# MCU.net
KiCad netlist of a schematic drawn in EAGLE
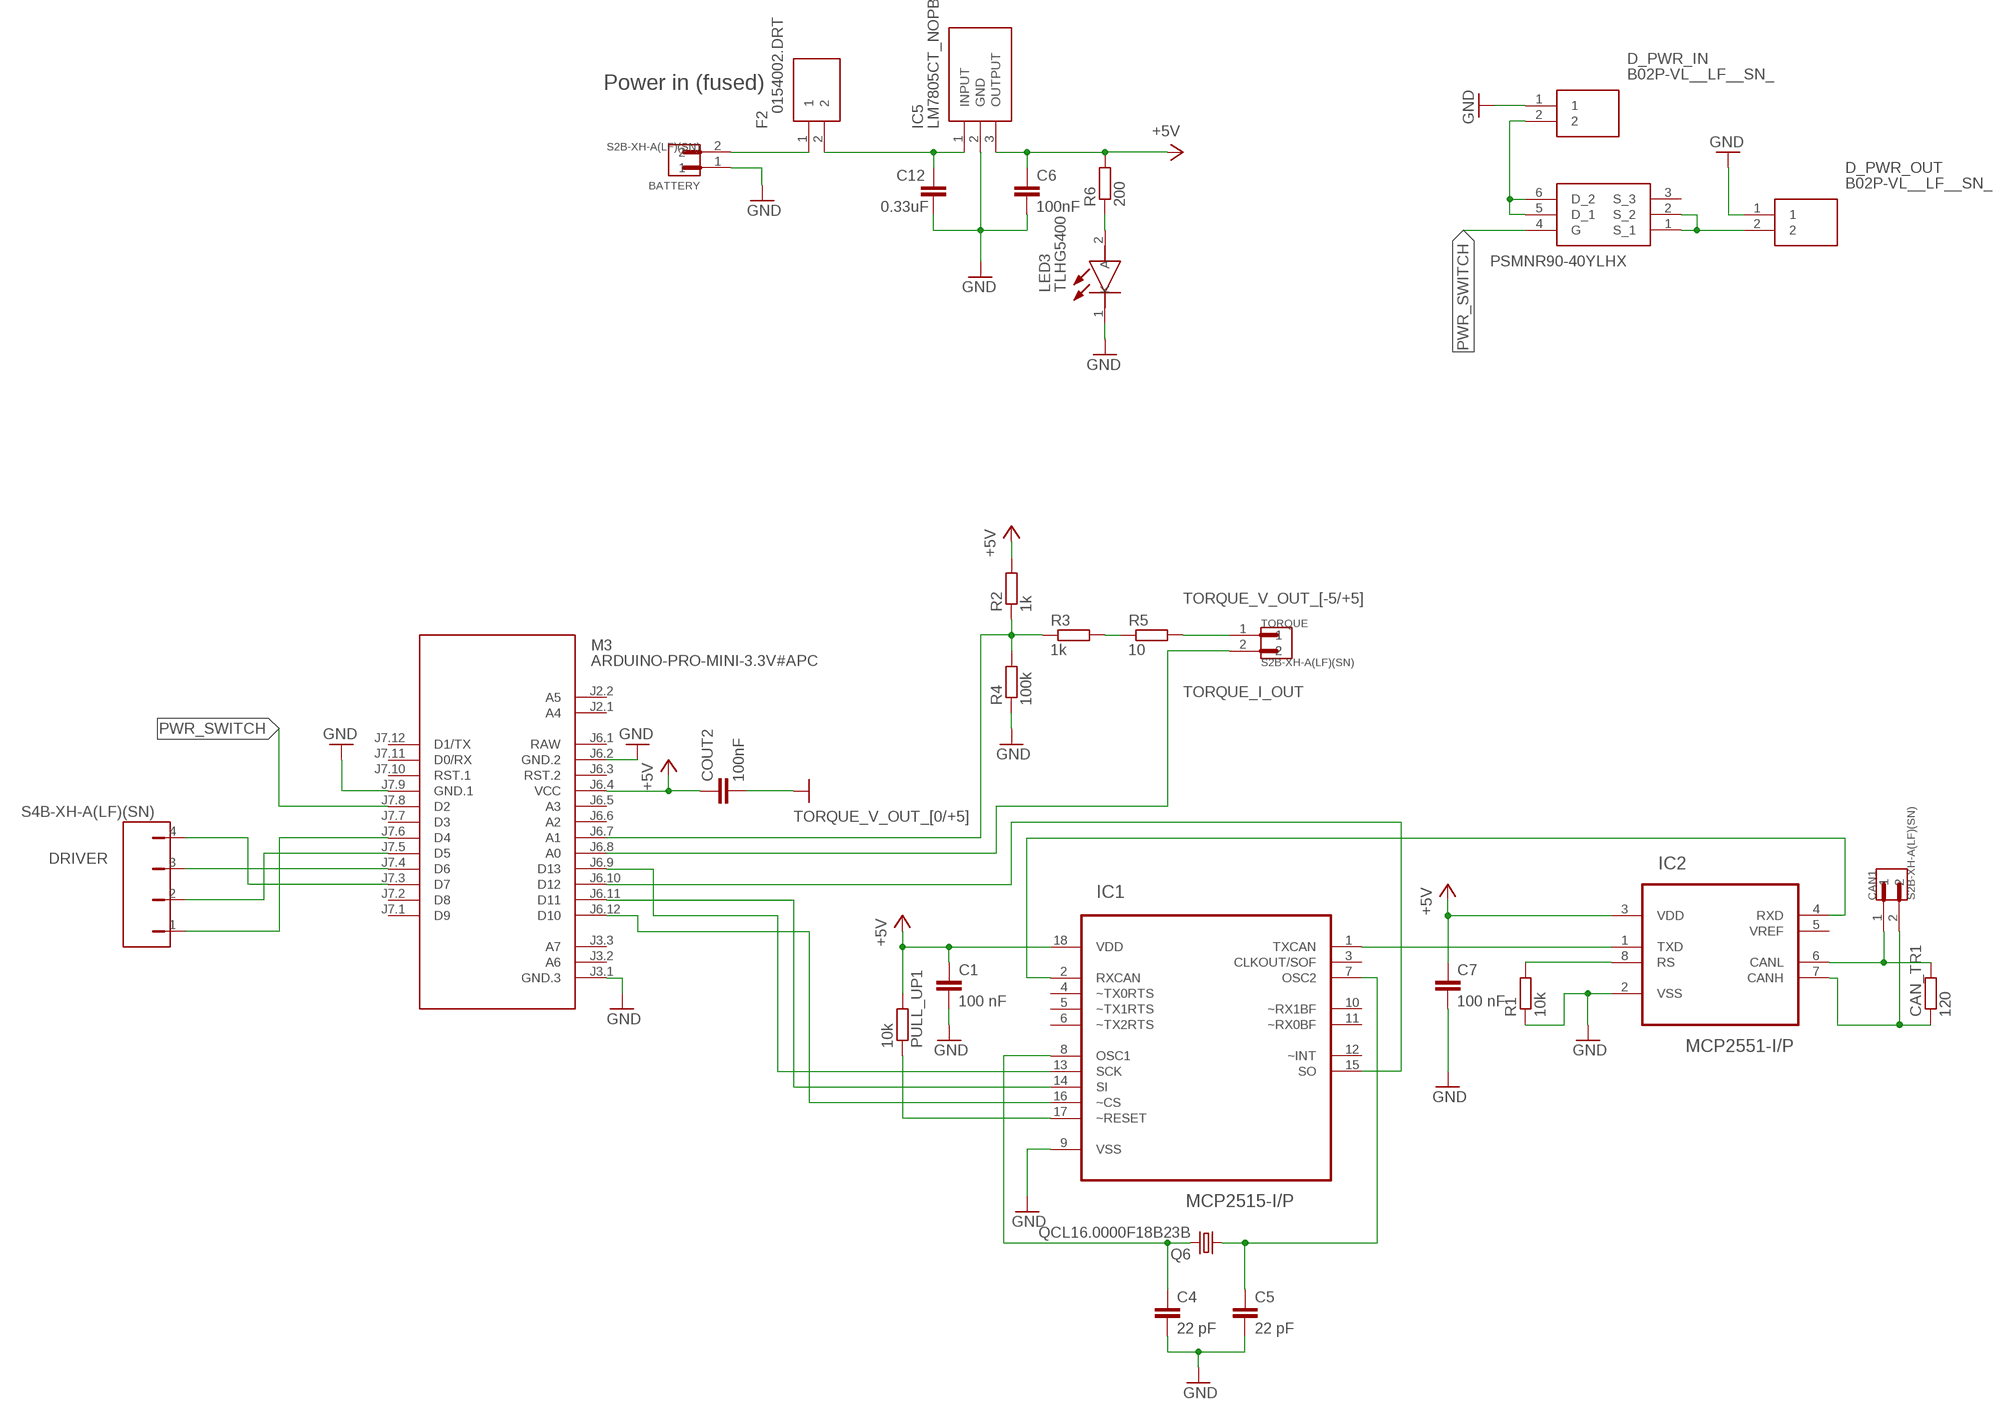
[diagram p0: schematic, sheet 1]

(export (version "E")
  (design (tool "Eeschema 10.0.6"))
  (components
    (comp (ref "BATTERY")
      (value "S2B-XH-A(LF)(SN)")
      (footprint "eagle-import:JST_S2B-XH-A(LF)(SN)")
      (fields
        (field (name "DIGI-KEY_PART_NUMBER") "455-2257-ND")
        (field (name "MF") "JST Sales")
        (field (name "MP") "S2B-XH-A_LF__SN_")
      )
      (libsource (lib "eagle-import") (part "S2B-XH-A(LF)(SN)"))
    )
    (comp (ref "C1")
      (value "100 nF")
      (footprint "eagle-import:C0805")
      (libsource (lib "eagle-import") (part "C-EUC0805"))
    )
    (comp (ref "C4")
      (value "22 pF")
      (footprint "eagle-import:C0805")
      (libsource (lib "eagle-import") (part "C-EUC0805"))
    )
    (comp (ref "C5")
      (value "22 pF")
      (footprint "eagle-import:C0805")
      (libsource (lib "eagle-import") (part "C-EUC0805"))
    )
    (comp (ref "C6")
      (value "100nF")
      (footprint "eagle-import:C0805")
      (libsource (lib "eagle-import") (part "C-EUC0805"))
    )
    (comp (ref "C7")
      (value "100 nF")
      (footprint "eagle-import:C0805")
      (libsource (lib "eagle-import") (part "C-EUC0805"))
    )
    (comp (ref "C12")
      (value "0.33uF")
      (footprint "eagle-import:C0805")
      (libsource (lib "eagle-import") (part "C-EUC0805"))
    )
    (comp (ref "CAN1")
      (value "S2B-XH-A(LF)(SN)")
      (footprint "eagle-import:JST_S2B-XH-A(LF)(SN)")
      (fields
        (field (name "DIGI-KEY_PART_NUMBER") "455-2257-ND")
        (field (name "MF") "JST Sales")
        (field (name "MP") "S2B-XH-A_LF__SN_")
      )
      (libsource (lib "eagle-import") (part "S2B-XH-A(LF)(SN)"))
    )
    (comp (ref "CAN_TR1")
      (value "120")
      (footprint "eagle-import:R0805")
      (libsource (lib "eagle-import") (part "R-EU_R0805"))
    )
    (comp (ref "COUT2")
      (value "100nF")
      (footprint "eagle-import:C0805")
      (libsource (lib "eagle-import") (part "C-EUC0805"))
    )
    (comp (ref "DRIVER")
      (value "S4B-XH-A(LF)(SN)")
      (footprint "eagle-import:S4B-XH-A(LF)(SN)")
      (fields (field (name "MF") "JST Sales") (field (name "MP") "S4B-XH-A_LF__SN_"))
      (libsource (lib "eagle-import") (part "S4B-XH-A(LF)(SN)"))
    )
    (comp (ref "D_PWR_IN")
      (value "B02P-VL__LF__SN_")
      (footprint "eagle-import:SHDR2W180P0X620_1X2_1340X1320X")
      (fields
        (field (name "MANUFACTURER_PART_NUMBER") "B02P-VL (LF)(SN)")
        (field (name "RS_PART_NUMBER") "8201093P")
      )
      (libsource (lib "eagle-import") (part "B02P-VL__LF__SN_"))
    )
    (comp (ref "D_PWR_OUT")
      (value "B02P-VL__LF__SN_")
      (footprint "eagle-import:SHDR2W180P0X620_1X2_1340X1320X")
      (fields
        (field (name "MANUFACTURER_PART_NUMBER") "B02P-VL (LF)(SN)")
        (field (name "RS_PART_NUMBER") "8201093P")
      )
      (libsource (lib "eagle-import") (part "B02P-VL__LF__SN_"))
    )
    (comp (ref "F2")
      (value "0154002.DRT")
      (footprint "eagle-import:FUSM9750X381N")
      (fields (field (name "MOUSER_PART_NUMBER") "576-0154002.DRT"))
      (libsource (lib "eagle-import") (part "0154002.DRT"))
    )
    (comp (ref "IC1")
      (value "MCP2515-I/P")
      (footprint "eagle-import:DIP254P762X432-18")
      (fields (field (name "MF") "Microchip"))
      (libsource (lib "eagle-import") (part "MCP2515-I/P"))
    )
    (comp (ref "IC2")
      (value "MCP2551-I/P")
      (footprint "eagle-import:DIP254P762X432-8")
      (fields (field (name "MF") "Microchip"))
      (libsource (lib "eagle-import") (part "MCP2551-I/P"))
    )
    (comp (ref "IC5")
      (value "LM7805CT_NOPB")
      (footprint "eagle-import:TO254P470X1028X1955-3P")
      (fields
        (field (name "MANUFACTURER_PART_NUMBER") "LM7805CT/NOPB")
        (field (name "MOUSER_PART_NUMBER") "926-LM7805CT/NOPB")
      )
      (libsource (lib "eagle-import") (part "LM7805CT_NOPB"))
    )
    (comp (ref "LED3")
      (value "TLHG5400")
      (footprint "eagle-import:TLHG5400")
      (fields (field (name "MOUSER_PART_NUMBER") "78-TLHG5400"))
      (libsource (lib "eagle-import") (part "TLHG5400"))
    )
    (comp (ref "M3")
      (value "ARDUINO-PRO-MINI-3.3V#APC")
      (footprint "eagle-import:ARDUINO-PRO-MINI#APC")
      (libsource (lib "eagle-import") (part "ARDUINO-PRO-MINI-#APC3.3V"))
    )
    (comp (ref "PULL_UP1")
      (value "10k")
      (footprint "eagle-import:R0805")
      (libsource (lib "eagle-import") (part "R-EU_R0805"))
    )
    (comp (ref "Q1")
      (value "PSMNR90-40YLHX")
      (footprint "eagle-import:PSMNR9040YLHX")
      (fields (field (name "MOUSER_PART_NUMBER") "771-PSMNR90-40YLHX"))
      (libsource (lib "eagle-import") (part "PSMNR90-40YLHX"))
    )
    (comp (ref "Q6")
      (value "QCL16.0000F18B23B")
      (footprint "eagle-import:HC49_S")
      (libsource (lib "eagle-import") (part "CRYSTALHC49S"))
    )
    (comp (ref "R1")
      (value "10k")
      (footprint "eagle-import:R0805")
      (libsource (lib "eagle-import") (part "R-EU_R0805"))
    )
    (comp (ref "R2")
      (value "1k")
      (footprint "eagle-import:R0805")
      (libsource (lib "eagle-import") (part "R-EU_R0805"))
    )
    (comp (ref "R3")
      (value "1k")
      (footprint "eagle-import:R0805")
      (libsource (lib "eagle-import") (part "R-EU_R0805"))
    )
    (comp (ref "R4")
      (value "100k")
      (footprint "eagle-import:R0805")
      (libsource (lib "eagle-import") (part "R-EU_R0805"))
    )
    (comp (ref "R5")
      (value "10")
      (footprint "eagle-import:R0805")
      (libsource (lib "eagle-import") (part "R-EU_R0805"))
    )
    (comp (ref "R6")
      (value "200")
      (footprint "eagle-import:R0805")
      (libsource (lib "eagle-import") (part "R-EU_R0805"))
    )
    (comp (ref "TORQUE")
      (value "S2B-XH-A(LF)(SN)")
      (footprint "eagle-import:JST_S2B-XH-A(LF)(SN)")
      (fields
        (field (name "DIGI-KEY_PART_NUMBER") "455-2257-ND")
        (field (name "MF") "JST Sales")
        (field (name "MP") "S2B-XH-A_LF__SN_")
      )
      (libsource (lib "eagle-import") (part "S2B-XH-A(LF)(SN)"))
    )
  )
  (nets
    (net (code "1") (name "+5V") (class "Default")
      (node (ref "C1") (pin "1") (pinfunction "1_1") (pintype "passive"))
      (node (ref "C6") (pin "1") (pinfunction "1_1") (pintype "passive"))
      (node (ref "C7") (pin "1") (pinfunction "1_1") (pintype "passive"))
      (node (ref "COUT2") (pin "1") (pinfunction "1_1") (pintype "passive"))
      (node (ref "IC1") (pin "18") (pinfunction "VDD_18") (pintype "power_in"))
      (node (ref "IC2") (pin "3") (pinfunction "VDD_3") (pintype "power_in"))
      (node (ref "IC5") (pin "3") (pinfunction "OUTPUT_3") (pintype "bidirectional"))
      (node (ref "M3") (pin "J6.4") (pinfunction "VCC_J6.4") (pintype "power_in"))
      (node (ref "PULL_UP1") (pin "2") (pinfunction "2_2") (pintype "passive"))
      (node (ref "R2") (pin "2") (pinfunction "2_2") (pintype "passive"))
      (node (ref "R6") (pin "2") (pinfunction "2_2") (pintype "passive"))
    )
    (net (code "2") (name "/RAW") (class "Default")
      (node (ref "M3") (pin "J6.1") (pinfunction "RAW_J6.1") (pintype "power_in"))
    )
    (net (code "3") (name "/TORQUE_I_OUT") (class "Default")
      (node (ref "M3") (pin "J6.8") (pinfunction "A0_J6.8") (pintype "bidirectional"))
      (node (ref "TORQUE") (pin "2") (pinfunction "2_2") (pintype "passive"))
    )
    (net (code "4") (name "/TORQUE_V_OUT_[-5{slash}+5]") (class "Default")
      (node (ref "R5") (pin "2") (pinfunction "2_2") (pintype "passive"))
      (node (ref "TORQUE") (pin "1") (pinfunction "1_1") (pintype "passive"))
    )
    (net (code "5") (name "/TORQUE_V_OUT_[0{slash}+5]") (class "Default")
      (node (ref "M3") (pin "J6.7") (pinfunction "A1_J6.7") (pintype "bidirectional"))
      (node (ref "R2") (pin "1") (pinfunction "1_1") (pintype "passive"))
      (node (ref "R3") (pin "1") (pinfunction "1_1") (pintype "passive"))
      (node (ref "R4") (pin "2") (pinfunction "2_2") (pintype "passive"))
    )
    (net (code "6") (name "GND") (class "Default")
      (node (ref "BATTERY") (pin "1") (pinfunction "1_1") (pintype "passive"))
      (node (ref "C1") (pin "2") (pinfunction "2_2") (pintype "passive"))
      (node (ref "C12") (pin "2") (pinfunction "2_2") (pintype "passive"))
      (node (ref "C4") (pin "2") (pinfunction "2_2") (pintype "passive"))
      (node (ref "C5") (pin "2") (pinfunction "2_2") (pintype "passive"))
      (node (ref "C6") (pin "2") (pinfunction "2_2") (pintype "passive"))
      (node (ref "C7") (pin "2") (pinfunction "2_2") (pintype "passive"))
      (node (ref "COUT2") (pin "2") (pinfunction "2_2") (pintype "passive"))
      (node (ref "D_PWR_IN") (pin "1") (pinfunction "1_1") (pintype "bidirectional"))
      (node (ref "D_PWR_OUT") (pin "1") (pinfunction "1_1") (pintype "bidirectional"))
      (node (ref "IC1") (pin "9") (pinfunction "VSS_9") (pintype "power_in"))
      (node (ref "IC2") (pin "2") (pinfunction "VSS_2") (pintype "power_in"))
      (node (ref "IC5") (pin "2") (pinfunction "GND_2") (pintype "bidirectional"))
      (node (ref "LED3") (pin "1") (pinfunction "K_1") (pintype "bidirectional"))
      (node (ref "M3") (pin "J3.1") (pinfunction "GND.3_J3.1") (pintype "bidirectional"))
      (node (ref "M3") (pin "J6.2") (pinfunction "GND.2_J6.2") (pintype "power_in"))
      (node (ref "M3") (pin "J7.9") (pinfunction "GND.1_J7.9") (pintype "power_in"))
      (node (ref "R1") (pin "1") (pinfunction "1_1") (pintype "passive"))
      (node (ref "R4") (pin "1") (pinfunction "1_1") (pintype "passive"))
    )
    (net (code "7") (name "Net-(BATTERY-Pad2)") (class "Default")
      (node (ref "BATTERY") (pin "2") (pinfunction "2_2") (pintype "passive"))
      (node (ref "F2") (pin "1") (pinfunction "1_1") (pintype "bidirectional"))
    )
    (net (code "8") (name "Net-(IC1-OSC1)") (class "Default")
      (node (ref "C4") (pin "1") (pinfunction "1_1") (pintype "passive"))
      (node (ref "IC1") (pin "8") (pinfunction "OSC1_8") (pintype "input"))
      (node (ref "Q6") (pin "2") (pinfunction "2_2") (pintype "passive"))
    )
    (net (code "9") (name "Net-(IC1-OSC2)") (class "Default")
      (node (ref "C5") (pin "1") (pinfunction "1_1") (pintype "passive"))
      (node (ref "IC1") (pin "7") (pinfunction "OSC2_7") (pintype "output"))
      (node (ref "Q6") (pin "1") (pinfunction "1_1") (pintype "passive"))
    )
    (net (code "10") (name "Net-(IC1-RXCAN)") (class "Default")
      (node (ref "IC1") (pin "2") (pinfunction "RXCAN_2") (pintype "input"))
      (node (ref "IC2") (pin "4") (pinfunction "RXD_4") (pintype "output"))
    )
    (net (code "11") (name "Net-(IC1-SCK)") (class "Default")
      (node (ref "IC1") (pin "13") (pinfunction "SCK_13") (pintype "input"))
      (node (ref "M3") (pin "J6.9") (pinfunction "D13_J6.9") (pintype "bidirectional"))
    )
    (net (code "12") (name "Net-(IC1-SI)") (class "Default")
      (node (ref "IC1") (pin "14") (pinfunction "SI_14") (pintype "input"))
      (node (ref "M3") (pin "J6.11") (pinfunction "D11_J6.11") (pintype "bidirectional"))
    )
    (net (code "13") (name "Net-(IC1-SO)") (class "Default")
      (node (ref "IC1") (pin "15") (pinfunction "SO_15") (pintype "output"))
      (node (ref "M3") (pin "J6.10") (pinfunction "D12_J6.10") (pintype "bidirectional"))
    )
    (net (code "14") (name "Net-(IC1-TXCAN)") (class "Default")
      (node (ref "IC1") (pin "1") (pinfunction "TXCAN_1") (pintype "output"))
      (node (ref "IC2") (pin "1") (pinfunction "TXD_1") (pintype "input"))
    )
    (net (code "15") (name "Net-(IC1-~{CS})") (class "Default")
      (node (ref "IC1") (pin "16") (pinfunction "~{CS}_16") (pintype "input"))
      (node (ref "M3") (pin "J6.12") (pinfunction "D10_J6.12") (pintype "bidirectional"))
    )
    (net (code "16") (name "Net-(IC1-~{RESET})") (class "Default")
      (node (ref "IC1") (pin "17") (pinfunction "~{RESET}_17") (pintype "input"))
      (node (ref "PULL_UP1") (pin "1") (pinfunction "1_1") (pintype "passive"))
    )
    (net (code "17") (name "Net-(IC2-CANH)") (class "Default")
      (node (ref "CAN1") (pin "2") (pinfunction "2_2") (pintype "passive"))
      (node (ref "CAN_TR1") (pin "1") (pinfunction "1_1") (pintype "passive"))
      (node (ref "IC2") (pin "7") (pinfunction "CANH_7") (pintype "bidirectional"))
    )
    (net (code "18") (name "Net-(IC2-CANL)") (class "Default")
      (node (ref "CAN1") (pin "1") (pinfunction "1_1") (pintype "passive"))
      (node (ref "CAN_TR1") (pin "2") (pinfunction "2_2") (pintype "passive"))
      (node (ref "IC2") (pin "6") (pinfunction "CANL_6") (pintype "bidirectional"))
    )
    (net (code "19") (name "Net-(IC2-RS)") (class "Default")
      (node (ref "IC2") (pin "8") (pinfunction "RS_8") (pintype "input"))
      (node (ref "R1") (pin "2") (pinfunction "2_2") (pintype "passive"))
    )
    (net (code "20") (name "Net-(IC5-INPUT)") (class "Default")
      (node (ref "C12") (pin "1") (pinfunction "1_1") (pintype "passive"))
      (node (ref "F2") (pin "2") (pinfunction "2_2") (pintype "bidirectional"))
      (node (ref "IC5") (pin "1") (pinfunction "INPUT_1") (pintype "bidirectional"))
    )
    (net (code "21") (name "Net-(LED3-A)") (class "Default")
      (node (ref "LED3") (pin "2") (pinfunction "A_2") (pintype "bidirectional"))
      (node (ref "R6") (pin "1") (pinfunction "1_1") (pintype "passive"))
    )
    (net (code "22") (name "Net-(M3-D4)") (class "Default")
      (node (ref "DRIVER") (pin "1") (pinfunction "1_1") (pintype "passive"))
      (node (ref "M3") (pin "J7.6") (pinfunction "D4_J7.6") (pintype "bidirectional"))
    )
    (net (code "23") (name "Net-(M3-D5)") (class "Default")
      (node (ref "DRIVER") (pin "2") (pinfunction "2_2") (pintype "passive"))
      (node (ref "M3") (pin "J7.5") (pinfunction "D5_J7.5") (pintype "bidirectional"))
    )
    (net (code "24") (name "Net-(M3-D6)") (class "Default")
      (node (ref "DRIVER") (pin "3") (pinfunction "3_3") (pintype "passive"))
      (node (ref "M3") (pin "J7.4") (pinfunction "D6_J7.4") (pintype "bidirectional"))
    )
    (net (code "25") (name "Net-(M3-D7)") (class "Default")
      (node (ref "DRIVER") (pin "4") (pinfunction "4_4") (pintype "passive"))
      (node (ref "M3") (pin "J7.3") (pinfunction "D7_J7.3") (pintype "bidirectional"))
    )
    (net (code "26") (name "Net-(Q1-D_1)") (class "Default")
      (node (ref "D_PWR_IN") (pin "2") (pinfunction "2_2") (pintype "bidirectional"))
      (node (ref "Q1") (pin "5") (pinfunction "D_1_5") (pintype "bidirectional"))
      (node (ref "Q1") (pin "6") (pinfunction "D_2_6") (pintype "bidirectional"))
    )
    (net (code "27") (name "Net-(Q1-S_1)") (class "Default")
      (node (ref "D_PWR_OUT") (pin "2") (pinfunction "2_2") (pintype "bidirectional"))
      (node (ref "Q1") (pin "1") (pinfunction "S_1_1") (pintype "bidirectional"))
      (node (ref "Q1") (pin "2") (pinfunction "S_2_2") (pintype "bidirectional"))
    )
    (net (code "28") (name "Net-(R3-Pad2)") (class "Default")
      (node (ref "R3") (pin "2") (pinfunction "2_2") (pintype "passive"))
      (node (ref "R5") (pin "1") (pinfunction "1_1") (pintype "passive"))
    )
    (net (code "29") (name "PWR_SWITCH") (class "Default")
      (node (ref "M3") (pin "J7.8") (pinfunction "D2_J7.8") (pintype "bidirectional"))
      (node (ref "Q1") (pin "4") (pinfunction "G_4") (pintype "bidirectional"))
    )
    (net (code "30") (name "unconnected-(IC1-CLKOUT{slash}SOF-Pad3)") (class "Default")
      (node (ref "IC1") (pin "3") (pinfunction "CLKOUT/SOF_3") (pintype "output"))
    )
    (net (code "31") (name "unconnected-(IC1-~{INT}-Pad12)") (class "Default")
      (node (ref "IC1") (pin "12") (pinfunction "~{INT}_12") (pintype "output"))
    )
    (net (code "32") (name "unconnected-(IC1-~{RX0BF}-Pad11)") (class "Default")
      (node (ref "IC1") (pin "11") (pinfunction "~{RX0BF}_11") (pintype "output"))
    )
    (net (code "33") (name "unconnected-(IC1-~{RX1BF}-Pad10)") (class "Default")
      (node (ref "IC1") (pin "10") (pinfunction "~{RX1BF}_10") (pintype "output"))
    )
    (net (code "34") (name "unconnected-(IC1-~{TX0RTS}-Pad4)") (class "Default")
      (node (ref "IC1") (pin "4") (pinfunction "~{TX0RTS}_4") (pintype "input"))
    )
    (net (code "35") (name "unconnected-(IC1-~{TX1RTS}-Pad5)") (class "Default")
      (node (ref "IC1") (pin "5") (pinfunction "~{TX1RTS}_5") (pintype "input"))
    )
    (net (code "36") (name "unconnected-(IC1-~{TX2RTS}-Pad6)") (class "Default")
      (node (ref "IC1") (pin "6") (pinfunction "~{TX2RTS}_6") (pintype "input"))
    )
    (net (code "37") (name "unconnected-(IC2-VREF-Pad5)") (class "Default")
      (node (ref "IC2") (pin "5") (pinfunction "VREF_5") (pintype "output"))
    )
    (net (code "38") (name "unconnected-(M3-A2-PadJ6.6)") (class "Default")
      (node (ref "M3") (pin "J6.6") (pinfunction "A2_J6.6") (pintype "bidirectional"))
    )
    (net (code "39") (name "unconnected-(M3-A3-PadJ6.5)") (class "Default")
      (node (ref "M3") (pin "J6.5") (pinfunction "A3_J6.5") (pintype "bidirectional"))
    )
    (net (code "40") (name "unconnected-(M3-A4-PadJ2.1)") (class "Default")
      (node (ref "M3") (pin "J2.1") (pinfunction "A4_J2.1") (pintype "bidirectional"))
    )
    (net (code "41") (name "unconnected-(M3-A5-PadJ2.2)") (class "Default")
      (node (ref "M3") (pin "J2.2") (pinfunction "A5_J2.2") (pintype "bidirectional"))
    )
    (net (code "42") (name "unconnected-(M3-A6-PadJ3.2)") (class "Default")
      (node (ref "M3") (pin "J3.2") (pinfunction "A6_J3.2") (pintype "bidirectional"))
    )
    (net (code "43") (name "unconnected-(M3-A7-PadJ3.3)") (class "Default")
      (node (ref "M3") (pin "J3.3") (pinfunction "A7_J3.3") (pintype "bidirectional"))
    )
    (net (code "44") (name "unconnected-(M3-D0{slash}RX-PadJ7.11)") (class "Default")
      (node (ref "M3") (pin "J7.11") (pinfunction "D0/RX_J7.11") (pintype "bidirectional"))
    )
    (net (code "45") (name "unconnected-(M3-D1{slash}TX-PadJ7.12)") (class "Default")
      (node (ref "M3") (pin "J7.12") (pinfunction "D1/TX_J7.12") (pintype "bidirectional"))
    )
    (net (code "46") (name "unconnected-(M3-D3-PadJ7.7)") (class "Default")
      (node (ref "M3") (pin "J7.7") (pinfunction "D3_J7.7") (pintype "bidirectional"))
    )
    (net (code "47") (name "unconnected-(M3-D8-PadJ7.2)") (class "Default")
      (node (ref "M3") (pin "J7.2") (pinfunction "D8_J7.2") (pintype "bidirectional"))
    )
    (net (code "48") (name "unconnected-(M3-D9-PadJ7.1)") (class "Default")
      (node (ref "M3") (pin "J7.1") (pinfunction "D9_J7.1") (pintype "bidirectional"))
    )
    (net (code "49") (name "unconnected-(M3-RST.1-PadJ7.10)") (class "Default")
      (node (ref "M3") (pin "J7.10") (pinfunction "RST.1_J7.10") (pintype "bidirectional"))
    )
    (net (code "50") (name "unconnected-(M3-RST.2-PadJ6.3)") (class "Default")
      (node (ref "M3") (pin "J6.3") (pinfunction "RST.2_J6.3") (pintype "bidirectional"))
    )
    (net (code "51") (name "unconnected-(Q1-S_3-Pad3)") (class "Default")
      (node (ref "Q1") (pin "3") (pinfunction "S_3_3") (pintype "bidirectional"))
    )
  )
)
